# Sheet1.net
KiCad netlist of a schematic drawn in Altium Designer
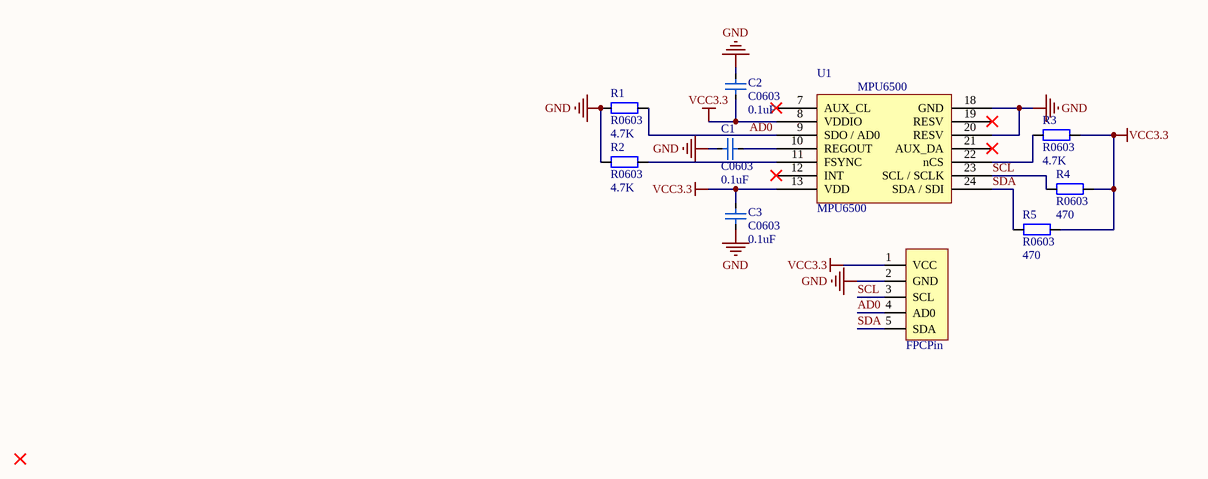
[diagram p0: Sheet1.SchDoc]

(export (version "E")
  (design (tool "Eeschema 10.0.6"))
  (components
    (comp (ref "*") (value "FPCPin") (footprint "FPCPin_5") (libsource (lib "Schlib1") (part "FPCPin")))
    (comp (ref "C1")
      (value "C0603")
      (footprint "CAPC1608X09N")
      (fields (field (name "ALTIUM_VALUE") "0.1uF"))
      (libsource (lib "Schlib1") (part "C0603"))
    )
    (comp (ref "C2")
      (value "C0603")
      (footprint "CAPC1608X09N")
      (fields (field (name "ALTIUM_VALUE") "0.1uF"))
      (libsource (lib "Schlib1") (part "C0603"))
    )
    (comp (ref "C3")
      (value "C0603")
      (footprint "CAPC1608X09N")
      (fields (field (name "ALTIUM_VALUE") "0.1uF"))
      (libsource (lib "Schlib1") (part "C0603"))
    )
    (comp (ref "R1")
      (value "R0603")
      (footprint "RESC1608X09N")
      (fields (field (name "ALTIUM_VALUE") "4.7K"))
      (libsource (lib "Schlib1") (part "R0603"))
    )
    (comp (ref "R2")
      (value "R0603")
      (footprint "RESC1608X09N")
      (fields (field (name "ALTIUM_VALUE") "4.7K"))
      (libsource (lib "Schlib1") (part "R0603"))
    )
    (comp (ref "R3")
      (value "R0603")
      (footprint "RESC1608X09N")
      (fields (field (name "ALTIUM_VALUE") "4.7K"))
      (libsource (lib "Schlib1") (part "R0603"))
    )
    (comp (ref "R4")
      (value "R0603")
      (footprint "RESC1608X09N")
      (fields (field (name "ALTIUM_VALUE") "470"))
      (libsource (lib "Schlib1") (part "R0603"))
    )
    (comp (ref "R5")
      (value "R0603")
      (footprint "RESC1608X09N")
      (fields (field (name "ALTIUM_VALUE") "470"))
      (libsource (lib "Schlib1") (part "R0603"))
    )
    (comp (ref "U1")
      (value "MPU6500")
      (footprint "QFN40P300X300X90_HS-25N")
      (libsource (lib "Schlib1") (part "Component_1"))
    )
  )
  (nets
    (net (code "1") (name "/AD0") (class "Default")
      (node (ref "*") (pin "4") (pinfunction "AD0_4") (pintype "passive"))
      (node (ref "R1") (pin "1") (pinfunction "1_1") (pintype "passive"))
      (node (ref "U1") (pin "9") (pinfunction "SDO_/_AD0_9") (pintype "passive"))
    )
    (net (code "2") (name "/SCL") (class "Default")
      (node (ref "*") (pin "3") (pinfunction "SCL_3") (pintype "passive"))
      (node (ref "R4") (pin "2") (pinfunction "2_2") (pintype "passive"))
      (node (ref "U1") (pin "23") (pinfunction "SCL_/_SCLK_23") (pintype "passive"))
    )
    (net (code "3") (name "/SDA") (class "Default")
      (node (ref "*") (pin "5") (pinfunction "SDA_5") (pintype "passive"))
      (node (ref "R5") (pin "2") (pinfunction "2_2") (pintype "passive"))
      (node (ref "U1") (pin "24") (pinfunction "SDA_/_SDI_24") (pintype "passive"))
    )
    (net (code "4") (name "GND") (class "Default")
      (node (ref "*") (pin "2") (pinfunction "GND_2") (pintype "passive"))
      (node (ref "C1") (pin "1") (pinfunction "1_1") (pintype "passive"))
      (node (ref "C2") (pin "1") (pinfunction "1_1") (pintype "passive"))
      (node (ref "C3") (pin "2") (pinfunction "2_2") (pintype "passive"))
      (node (ref "R1") (pin "2") (pinfunction "2_2") (pintype "passive"))
      (node (ref "R2") (pin "2") (pinfunction "2_2") (pintype "passive"))
      (node (ref "U1") (pin "18") (pinfunction "GND_18") (pintype "passive"))
      (node (ref "U1") (pin "20") (pinfunction "RESV_20") (pintype "passive"))
    )
    (net (code "5") (name "Net-(U1-FSYNC)") (class "Default")
      (node (ref "R2") (pin "1") (pinfunction "1_1") (pintype "passive"))
      (node (ref "U1") (pin "11") (pinfunction "FSYNC_11") (pintype "passive"))
    )
    (net (code "6") (name "Net-(U1-REGOUT)") (class "Default")
      (node (ref "C1") (pin "2") (pinfunction "2_2") (pintype "passive"))
      (node (ref "U1") (pin "10") (pinfunction "REGOUT_10") (pintype "passive"))
    )
    (net (code "7") (name "Net-(U1-nCS)") (class "Default")
      (node (ref "R3") (pin "2") (pinfunction "2_2") (pintype "passive"))
      (node (ref "U1") (pin "22") (pinfunction "nCS_22") (pintype "passive"))
    )
    (net (code "8") (name "VCC3.3") (class "Default")
      (node (ref "*") (pin "1") (pinfunction "VCC_1") (pintype "passive"))
      (node (ref "C2") (pin "2") (pinfunction "2_2") (pintype "passive"))
      (node (ref "C3") (pin "1") (pinfunction "1_1") (pintype "passive"))
      (node (ref "R3") (pin "1") (pinfunction "1_1") (pintype "passive"))
      (node (ref "R4") (pin "1") (pinfunction "1_1") (pintype "passive"))
      (node (ref "R5") (pin "1") (pinfunction "1_1") (pintype "passive"))
      (node (ref "U1") (pin "13") (pinfunction "VDD_13") (pintype "passive"))
      (node (ref "U1") (pin "8") (pinfunction "VDDIO_8") (pintype "passive"))
    )
    (net (code "9") (name "unconnected-(U1-AUX_CL-Pad7)") (class "Default")
      (node (ref "U1") (pin "7") (pinfunction "AUX_CL_7") (pintype "passive+no_connect"))
    )
    (net (code "10") (name "unconnected-(U1-AUX_DA-Pad21)") (class "Default")
      (node (ref "U1") (pin "21") (pinfunction "AUX_DA_21") (pintype "passive+no_connect"))
    )
    (net (code "11") (name "unconnected-(U1-INT-Pad12)") (class "Default")
      (node (ref "U1") (pin "12") (pinfunction "INT_12") (pintype "passive+no_connect"))
    )
    (net (code "12") (name "unconnected-(U1-RESV-Pad19)") (class "Default")
      (node (ref "U1") (pin "19") (pinfunction "RESV_19") (pintype "passive+no_connect"))
    )
  )
)
